# Multiplier.net
KiCad netlist of a schematic drawn in EAGLE
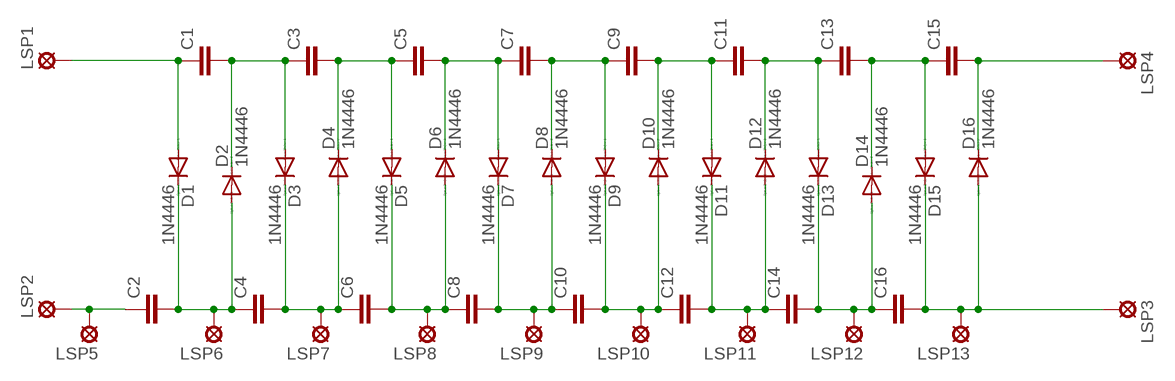
[diagram p0: schematic, sheet 1]

(export (version "E")
  (design (tool "Eeschema 10.0.6"))
  (components
    (comp (ref "C1")
      (value "C5/4.5")
      (footprint "eagle-import:C5B4.5")
      (libsource (lib "eagle-import") (part "C5/4.5"))
    )
    (comp (ref "C2")
      (value "C5/4.5")
      (footprint "eagle-import:C5B4.5")
      (libsource (lib "eagle-import") (part "C5/4.5"))
    )
    (comp (ref "C3")
      (value "C5/4.5")
      (footprint "eagle-import:C5B4.5")
      (libsource (lib "eagle-import") (part "C5/4.5"))
    )
    (comp (ref "C4")
      (value "C5/4.5")
      (footprint "eagle-import:C5B4.5")
      (libsource (lib "eagle-import") (part "C5/4.5"))
    )
    (comp (ref "C5")
      (value "C5/4.5")
      (footprint "eagle-import:C5B4.5")
      (libsource (lib "eagle-import") (part "C5/4.5"))
    )
    (comp (ref "C6")
      (value "C5/4.5")
      (footprint "eagle-import:C5B4.5")
      (libsource (lib "eagle-import") (part "C5/4.5"))
    )
    (comp (ref "C7")
      (value "C5/4.5")
      (footprint "eagle-import:C5B4.5")
      (libsource (lib "eagle-import") (part "C5/4.5"))
    )
    (comp (ref "C8")
      (value "C5/4.5")
      (footprint "eagle-import:C5B4.5")
      (libsource (lib "eagle-import") (part "C5/4.5"))
    )
    (comp (ref "C9")
      (value "C5/4.5")
      (footprint "eagle-import:C5B4.5")
      (libsource (lib "eagle-import") (part "C5/4.5"))
    )
    (comp (ref "C10")
      (value "C5/4.5")
      (footprint "eagle-import:C5B4.5")
      (libsource (lib "eagle-import") (part "C5/4.5"))
    )
    (comp (ref "C11")
      (value "C5/4.5")
      (footprint "eagle-import:C5B4.5")
      (libsource (lib "eagle-import") (part "C5/4.5"))
    )
    (comp (ref "C12")
      (value "C5/4.5")
      (footprint "eagle-import:C5B4.5")
      (libsource (lib "eagle-import") (part "C5/4.5"))
    )
    (comp (ref "C13")
      (value "C5/4.5")
      (footprint "eagle-import:C5B4.5")
      (libsource (lib "eagle-import") (part "C5/4.5"))
    )
    (comp (ref "C14")
      (value "C5/4.5")
      (footprint "eagle-import:C5B4.5")
      (libsource (lib "eagle-import") (part "C5/4.5"))
    )
    (comp (ref "C15")
      (value "C5/4.5")
      (footprint "eagle-import:C5B4.5")
      (libsource (lib "eagle-import") (part "C5/4.5"))
    )
    (comp (ref "C16")
      (value "C5/4.5")
      (footprint "eagle-import:C5B4.5")
      (libsource (lib "eagle-import") (part "C5/4.5"))
    )
    (comp (ref "D1")
      (value "1N4446")
      (footprint "eagle-import:DO35-10")
      (libsource (lib "eagle-import") (part "1N4446"))
    )
    (comp (ref "D2")
      (value "1N4446")
      (footprint "eagle-import:DO35-10")
      (libsource (lib "eagle-import") (part "1N4446"))
    )
    (comp (ref "D3")
      (value "1N4446")
      (footprint "eagle-import:DO35-10")
      (libsource (lib "eagle-import") (part "1N4446"))
    )
    (comp (ref "D4")
      (value "1N4446")
      (footprint "eagle-import:DO35-10")
      (libsource (lib "eagle-import") (part "1N4446"))
    )
    (comp (ref "D5")
      (value "1N4446")
      (footprint "eagle-import:DO35-10")
      (libsource (lib "eagle-import") (part "1N4446"))
    )
    (comp (ref "D6")
      (value "1N4446")
      (footprint "eagle-import:DO35-10")
      (libsource (lib "eagle-import") (part "1N4446"))
    )
    (comp (ref "D7")
      (value "1N4446")
      (footprint "eagle-import:DO35-10")
      (libsource (lib "eagle-import") (part "1N4446"))
    )
    (comp (ref "D8")
      (value "1N4446")
      (footprint "eagle-import:DO35-10")
      (libsource (lib "eagle-import") (part "1N4446"))
    )
    (comp (ref "D9")
      (value "1N4446")
      (footprint "eagle-import:DO35-10")
      (libsource (lib "eagle-import") (part "1N4446"))
    )
    (comp (ref "D10")
      (value "1N4446")
      (footprint "eagle-import:DO35-10")
      (libsource (lib "eagle-import") (part "1N4446"))
    )
    (comp (ref "D11")
      (value "1N4446")
      (footprint "eagle-import:DO35-10")
      (libsource (lib "eagle-import") (part "1N4446"))
    )
    (comp (ref "D12")
      (value "1N4446")
      (footprint "eagle-import:DO35-10")
      (libsource (lib "eagle-import") (part "1N4446"))
    )
    (comp (ref "D13")
      (value "1N4446")
      (footprint "eagle-import:DO35-10")
      (libsource (lib "eagle-import") (part "1N4446"))
    )
    (comp (ref "D14")
      (value "1N4446")
      (footprint "eagle-import:DO35-10")
      (libsource (lib "eagle-import") (part "1N4446"))
    )
    (comp (ref "D15")
      (value "1N4446")
      (footprint "eagle-import:DO35-10")
      (libsource (lib "eagle-import") (part "1N4446"))
    )
    (comp (ref "D16")
      (value "1N4446")
      (footprint "eagle-import:DO35-10")
      (libsource (lib "eagle-import") (part "1N4446"))
    )
    (comp (ref "LSP1")
      (value "LSP10")
      (footprint "eagle-import:LSP10")
      (libsource (lib "eagle-import") (part "LSP10"))
    )
    (comp (ref "LSP2")
      (value "LSP10")
      (footprint "eagle-import:LSP10")
      (libsource (lib "eagle-import") (part "LSP10"))
    )
    (comp (ref "LSP3")
      (value "LSP10")
      (footprint "eagle-import:LSP10")
      (libsource (lib "eagle-import") (part "LSP10"))
    )
    (comp (ref "LSP4")
      (value "LSP10")
      (footprint "eagle-import:LSP10")
      (libsource (lib "eagle-import") (part "LSP10"))
    )
    (comp (ref "LSP5")
      (value "LSP10")
      (footprint "eagle-import:LSP10")
      (libsource (lib "eagle-import") (part "LSP10"))
    )
    (comp (ref "LSP6")
      (value "LSP10")
      (footprint "eagle-import:LSP10")
      (libsource (lib "eagle-import") (part "LSP10"))
    )
    (comp (ref "LSP7")
      (value "LSP10")
      (footprint "eagle-import:LSP10")
      (libsource (lib "eagle-import") (part "LSP10"))
    )
    (comp (ref "LSP8")
      (value "LSP10")
      (footprint "eagle-import:LSP10")
      (libsource (lib "eagle-import") (part "LSP10"))
    )
    (comp (ref "LSP9")
      (value "LSP10")
      (footprint "eagle-import:LSP10")
      (libsource (lib "eagle-import") (part "LSP10"))
    )
    (comp (ref "LSP10")
      (value "LSP10")
      (footprint "eagle-import:LSP10")
      (libsource (lib "eagle-import") (part "LSP10"))
    )
    (comp (ref "LSP11")
      (value "LSP10")
      (footprint "eagle-import:LSP10")
      (libsource (lib "eagle-import") (part "LSP10"))
    )
    (comp (ref "LSP12")
      (value "LSP10")
      (footprint "eagle-import:LSP10")
      (libsource (lib "eagle-import") (part "LSP10"))
    )
    (comp (ref "LSP13")
      (value "LSP10")
      (footprint "eagle-import:LSP10")
      (libsource (lib "eagle-import") (part "LSP10"))
    )
  )
  (nets
    (net (code "1") (name "Net-(C1-Pad1)") (class "Default")
      (node (ref "C1") (pin "1") (pinfunction "1_1") (pintype "passive"))
      (node (ref "D1") (pin "A") (pinfunction "A_A") (pintype "passive"))
      (node (ref "LSP1") (pin "MP") (pinfunction "MP_MP") (pintype "passive"))
    )
    (net (code "2") (name "Net-(C1-Pad2)") (class "Default")
      (node (ref "C1") (pin "2") (pinfunction "2_2") (pintype "passive"))
      (node (ref "C3") (pin "1") (pinfunction "1_1") (pintype "passive"))
      (node (ref "D2") (pin "C") (pinfunction "C_C") (pintype "passive"))
      (node (ref "D3") (pin "A") (pinfunction "A_A") (pintype "passive"))
    )
    (net (code "3") (name "Net-(C2-Pad1)") (class "Default")
      (node (ref "C2") (pin "1") (pinfunction "1_1") (pintype "passive"))
      (node (ref "LSP2") (pin "MP") (pinfunction "MP_MP") (pintype "passive"))
      (node (ref "LSP5") (pin "MP") (pinfunction "MP_MP") (pintype "passive"))
    )
    (net (code "4") (name "Net-(C2-Pad2)") (class "Default")
      (node (ref "C2") (pin "2") (pinfunction "2_2") (pintype "passive"))
      (node (ref "C4") (pin "1") (pinfunction "1_1") (pintype "passive"))
      (node (ref "D1") (pin "C") (pinfunction "C_C") (pintype "passive"))
      (node (ref "D2") (pin "A") (pinfunction "A_A") (pintype "passive"))
      (node (ref "LSP6") (pin "MP") (pinfunction "MP_MP") (pintype "passive"))
    )
    (net (code "5") (name "Net-(C3-Pad2)") (class "Default")
      (node (ref "C3") (pin "2") (pinfunction "2_2") (pintype "passive"))
      (node (ref "C5") (pin "1") (pinfunction "1_1") (pintype "passive"))
      (node (ref "D4") (pin "C") (pinfunction "C_C") (pintype "passive"))
      (node (ref "D5") (pin "A") (pinfunction "A_A") (pintype "passive"))
    )
    (net (code "6") (name "Net-(C4-Pad2)") (class "Default")
      (node (ref "C4") (pin "2") (pinfunction "2_2") (pintype "passive"))
      (node (ref "C6") (pin "1") (pinfunction "1_1") (pintype "passive"))
      (node (ref "D3") (pin "C") (pinfunction "C_C") (pintype "passive"))
      (node (ref "D4") (pin "A") (pinfunction "A_A") (pintype "passive"))
      (node (ref "LSP7") (pin "MP") (pinfunction "MP_MP") (pintype "passive"))
    )
    (net (code "7") (name "Net-(C5-Pad2)") (class "Default")
      (node (ref "C5") (pin "2") (pinfunction "2_2") (pintype "passive"))
      (node (ref "C7") (pin "1") (pinfunction "1_1") (pintype "passive"))
      (node (ref "D6") (pin "C") (pinfunction "C_C") (pintype "passive"))
      (node (ref "D7") (pin "A") (pinfunction "A_A") (pintype "passive"))
    )
    (net (code "8") (name "Net-(C6-Pad2)") (class "Default")
      (node (ref "C6") (pin "2") (pinfunction "2_2") (pintype "passive"))
      (node (ref "C8") (pin "1") (pinfunction "1_1") (pintype "passive"))
      (node (ref "D5") (pin "C") (pinfunction "C_C") (pintype "passive"))
      (node (ref "D6") (pin "A") (pinfunction "A_A") (pintype "passive"))
      (node (ref "LSP8") (pin "MP") (pinfunction "MP_MP") (pintype "passive"))
    )
    (net (code "9") (name "Net-(C7-Pad2)") (class "Default")
      (node (ref "C7") (pin "2") (pinfunction "2_2") (pintype "passive"))
      (node (ref "C9") (pin "1") (pinfunction "1_1") (pintype "passive"))
      (node (ref "D8") (pin "C") (pinfunction "C_C") (pintype "passive"))
      (node (ref "D9") (pin "A") (pinfunction "A_A") (pintype "passive"))
    )
    (net (code "10") (name "Net-(C10-Pad1)") (class "Default")
      (node (ref "C10") (pin "1") (pinfunction "1_1") (pintype "passive"))
      (node (ref "C8") (pin "2") (pinfunction "2_2") (pintype "passive"))
      (node (ref "D7") (pin "C") (pinfunction "C_C") (pintype "passive"))
      (node (ref "D8") (pin "A") (pinfunction "A_A") (pintype "passive"))
      (node (ref "LSP9") (pin "MP") (pinfunction "MP_MP") (pintype "passive"))
    )
    (net (code "11") (name "Net-(C10-Pad2)") (class "Default")
      (node (ref "C10") (pin "2") (pinfunction "2_2") (pintype "passive"))
      (node (ref "C12") (pin "1") (pinfunction "1_1") (pintype "passive"))
      (node (ref "D10") (pin "A") (pinfunction "A_A") (pintype "passive"))
      (node (ref "D9") (pin "C") (pinfunction "C_C") (pintype "passive"))
      (node (ref "LSP10") (pin "MP") (pinfunction "MP_MP") (pintype "passive"))
    )
    (net (code "12") (name "Net-(C11-Pad1)") (class "Default")
      (node (ref "C11") (pin "1") (pinfunction "1_1") (pintype "passive"))
      (node (ref "C9") (pin "2") (pinfunction "2_2") (pintype "passive"))
      (node (ref "D10") (pin "C") (pinfunction "C_C") (pintype "passive"))
      (node (ref "D11") (pin "A") (pinfunction "A_A") (pintype "passive"))
    )
    (net (code "13") (name "Net-(C11-Pad2)") (class "Default")
      (node (ref "C11") (pin "2") (pinfunction "2_2") (pintype "passive"))
      (node (ref "C13") (pin "1") (pinfunction "1_1") (pintype "passive"))
      (node (ref "D12") (pin "C") (pinfunction "C_C") (pintype "passive"))
      (node (ref "D13") (pin "A") (pinfunction "A_A") (pintype "passive"))
    )
    (net (code "14") (name "Net-(C12-Pad2)") (class "Default")
      (node (ref "C12") (pin "2") (pinfunction "2_2") (pintype "passive"))
      (node (ref "C14") (pin "1") (pinfunction "1_1") (pintype "passive"))
      (node (ref "D11") (pin "C") (pinfunction "C_C") (pintype "passive"))
      (node (ref "D12") (pin "A") (pinfunction "A_A") (pintype "passive"))
      (node (ref "LSP11") (pin "MP") (pinfunction "MP_MP") (pintype "passive"))
    )
    (net (code "15") (name "Net-(C13-Pad2)") (class "Default")
      (node (ref "C13") (pin "2") (pinfunction "2_2") (pintype "passive"))
      (node (ref "C15") (pin "1") (pinfunction "1_1") (pintype "passive"))
      (node (ref "D14") (pin "C") (pinfunction "C_C") (pintype "passive"))
      (node (ref "D15") (pin "A") (pinfunction "A_A") (pintype "passive"))
    )
    (net (code "16") (name "Net-(C14-Pad2)") (class "Default")
      (node (ref "C14") (pin "2") (pinfunction "2_2") (pintype "passive"))
      (node (ref "C16") (pin "1") (pinfunction "1_1") (pintype "passive"))
      (node (ref "D13") (pin "C") (pinfunction "C_C") (pintype "passive"))
      (node (ref "D14") (pin "A") (pinfunction "A_A") (pintype "passive"))
      (node (ref "LSP12") (pin "MP") (pinfunction "MP_MP") (pintype "passive"))
    )
    (net (code "17") (name "Net-(C15-Pad2)") (class "Default")
      (node (ref "C15") (pin "2") (pinfunction "2_2") (pintype "passive"))
      (node (ref "D16") (pin "C") (pinfunction "C_C") (pintype "passive"))
      (node (ref "LSP4") (pin "MP") (pinfunction "MP_MP") (pintype "passive"))
    )
    (net (code "18") (name "Net-(C16-Pad2)") (class "Default")
      (node (ref "C16") (pin "2") (pinfunction "2_2") (pintype "passive"))
      (node (ref "D15") (pin "C") (pinfunction "C_C") (pintype "passive"))
      (node (ref "D16") (pin "A") (pinfunction "A_A") (pintype "passive"))
      (node (ref "LSP13") (pin "MP") (pinfunction "MP_MP") (pintype "passive"))
      (node (ref "LSP3") (pin "MP") (pinfunction "MP_MP") (pintype "passive"))
    )
  )
)
